# LCD_I2C.net
KiCad netlist of a schematic drawn in EAGLE
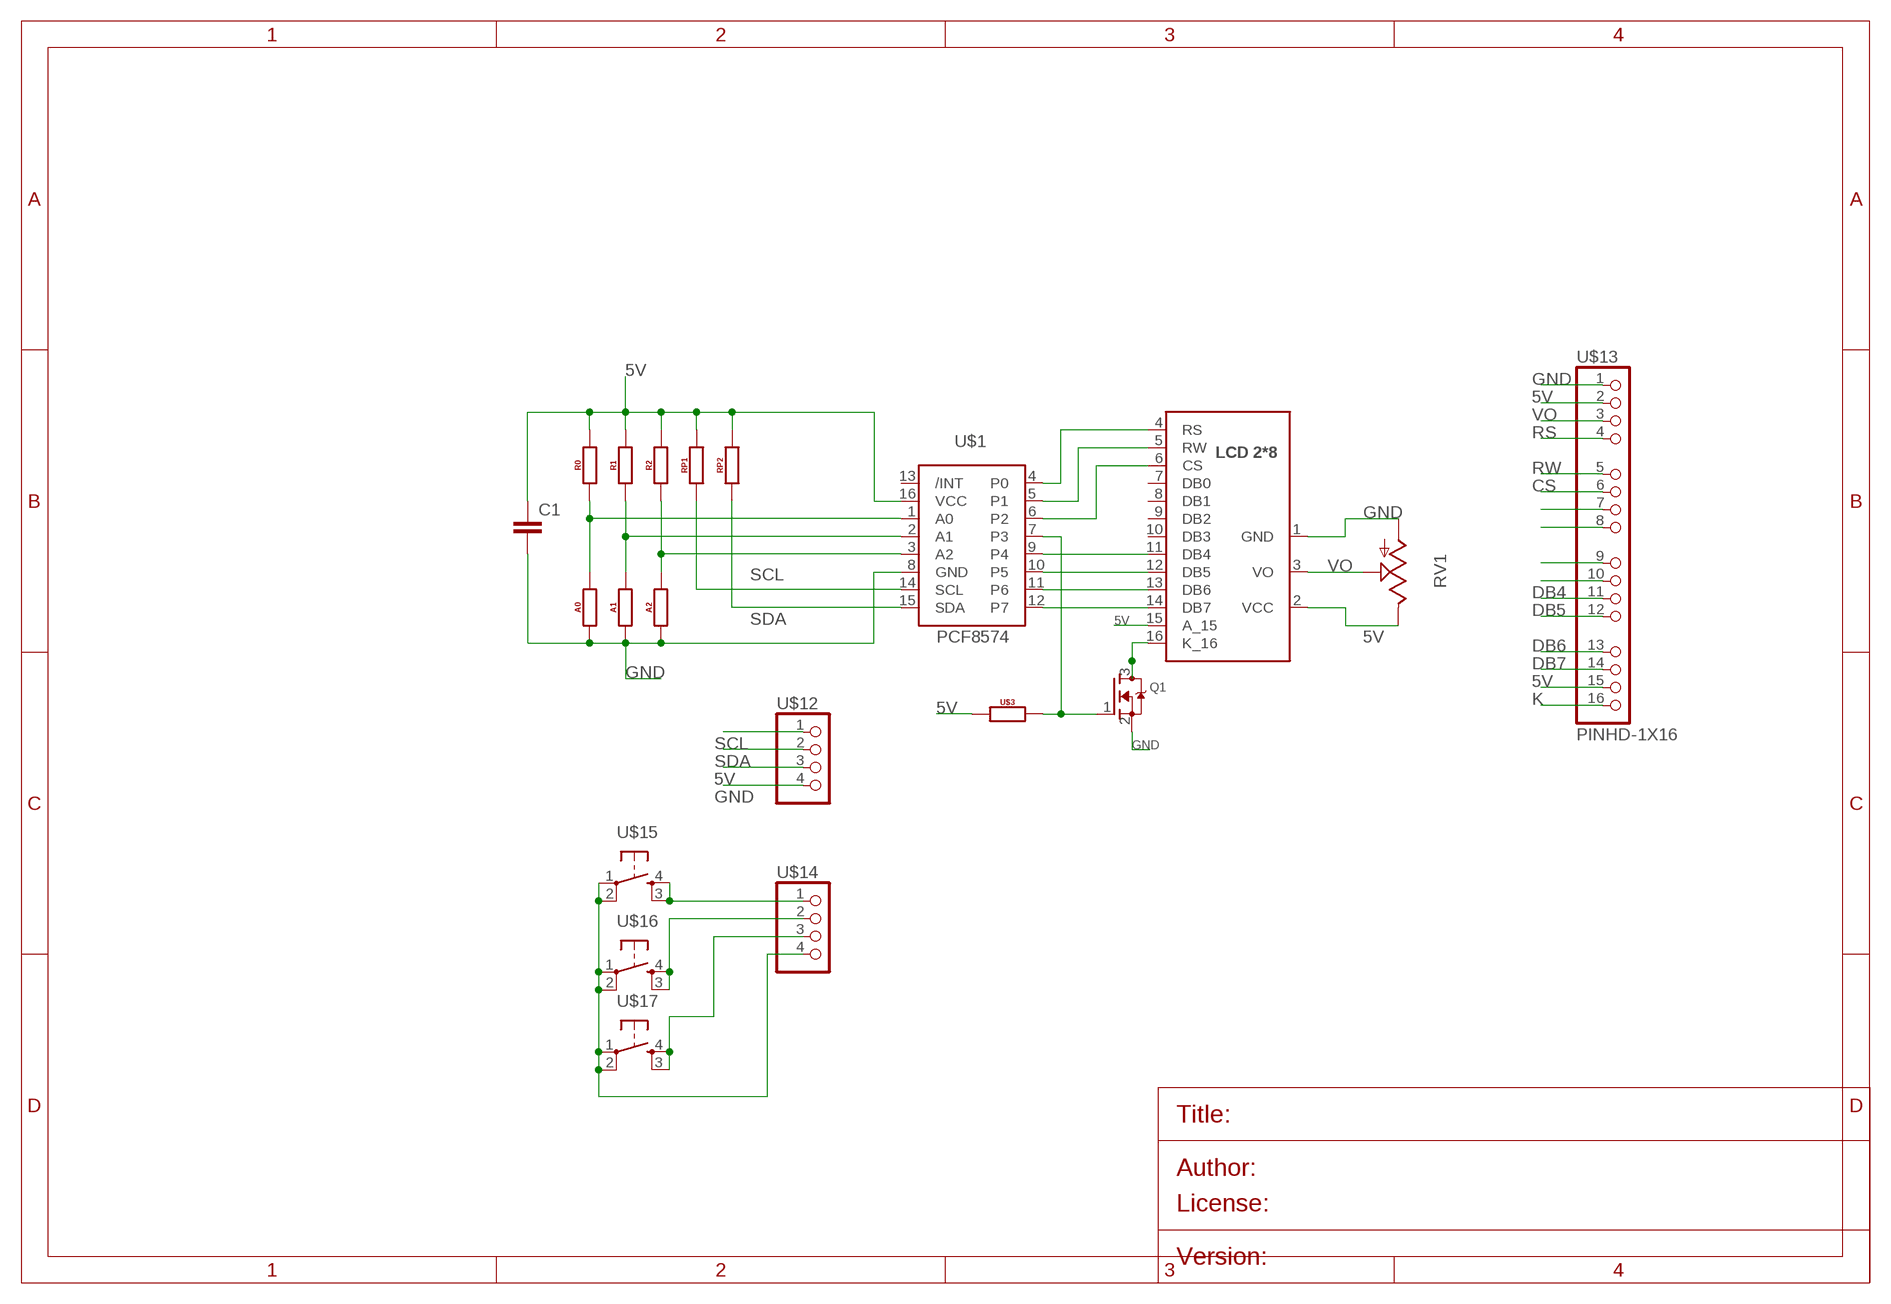
[diagram p0: schematic, sheet 1]

(export (version "E")
  (design (tool "Eeschema 10.0.6"))
  (components
    (comp (ref "A0")
      (value "RESISTOR0805")
      (footprint "eagle-import:0805")
      (libsource (lib "eagle-import") (part "RESISTOR0805"))
    )
    (comp (ref "A1")
      (value "RESISTOR0805")
      (footprint "eagle-import:0805")
      (libsource (lib "eagle-import") (part "RESISTOR0805"))
    )
    (comp (ref "A2")
      (value "RESISTOR0805")
      (footprint "eagle-import:0805")
      (libsource (lib "eagle-import") (part "RESISTOR0805"))
    )
    (comp (ref "C1")
      (value "CAPACITOR0805")
      (footprint "eagle-import:0805")
      (libsource (lib "eagle-import") (part "CAPACITOR0805"))
    )
    (comp (ref "Q1")
      (value "MOSFET-N")
      (footprint "eagle-import:SOT23-WIDE")
      (libsource (lib "eagle-import") (part "MOSFET-N"))
    )
    (comp (ref "R0")
      (value "RESISTOR0805")
      (footprint "eagle-import:0805")
      (libsource (lib "eagle-import") (part "RESISTOR0805"))
    )
    (comp (ref "R1")
      (value "RESISTOR0805")
      (footprint "eagle-import:0805")
      (libsource (lib "eagle-import") (part "RESISTOR0805"))
    )
    (comp (ref "R2")
      (value "RESISTOR0805")
      (footprint "eagle-import:0805")
      (libsource (lib "eagle-import") (part "RESISTOR0805"))
    )
    (comp (ref "RP1")
      (value "RESISTOR0805")
      (footprint "eagle-import:0805")
      (libsource (lib "eagle-import") (part "RESISTOR0805"))
    )
    (comp (ref "RP2")
      (value "RESISTOR0805")
      (footprint "eagle-import:0805")
      (libsource (lib "eagle-import") (part "RESISTOR0805"))
    )
    (comp (ref "RV1")
      (value "TRIM_POTB25P")
      (footprint "eagle-import:B25P")
      (libsource (lib "eagle-import") (part "TRIM_POTB25P"))
    )
    (comp (ref "U$1")
      (value "PCF8574")
      (footprint "eagle-import:SOIC16")
      (libsource (lib "eagle-import") (part "PCF8574"))
    )
    (comp (ref "U$2")
      (value "LCD_28_A")
      (footprint "eagle-import:LCD_2_8_A")
      (libsource (lib "eagle-import") (part "LCD_28_A"))
    )
    (comp (ref "U$3")
      (value "RESISTOR0805")
      (footprint "eagle-import:0805")
      (libsource (lib "eagle-import") (part "RESISTOR0805"))
    )
    (comp (ref "U$12")
      (value "PINHD-1X4_NO_SILK")
      (footprint "eagle-import:1X04_NO_SILK")
      (libsource (lib "eagle-import") (part "PINHD-1X4_NO_SILK"))
    )
    (comp (ref "U$13")
      (value "PINHD-1X16")
      (footprint "eagle-import:1X16_NO_SILK")
      (libsource (lib "eagle-import") (part "PINHD-1X16"))
    )
    (comp (ref "U$14")
      (value "PINHD-1X4_NO_SILK")
      (footprint "eagle-import:1X04_NO_SILK")
      (libsource (lib "eagle-import") (part "PINHD-1X4_NO_SILK"))
    )
    (comp (ref "U$15")
      (value "TACTILE_BUTTON_SMD")
      (footprint "eagle-import:TACTILE-BUTTON-SMD")
      (libsource (lib "eagle-import") (part "TACTILE_BUTTON_SMD"))
    )
    (comp (ref "U$16")
      (value "TACTILE_BUTTON_SMD")
      (footprint "eagle-import:TACTILE-BUTTON-SMD")
      (libsource (lib "eagle-import") (part "TACTILE_BUTTON_SMD"))
    )
    (comp (ref "U$17")
      (value "TACTILE_BUTTON_SMD")
      (footprint "eagle-import:TACTILE-BUTTON-SMD")
      (libsource (lib "eagle-import") (part "TACTILE_BUTTON_SMD"))
    )
  )
  (nets
    (net (code "1") (name "/5V") (class "Default")
      (node (ref "C1") (pin "1") (pinfunction "1_1") (pintype "passive"))
      (node (ref "R0") (pin "2") (pinfunction "2_2") (pintype "passive"))
      (node (ref "R1") (pin "2") (pinfunction "2_2") (pintype "passive"))
      (node (ref "R2") (pin "2") (pinfunction "2_2") (pintype "passive"))
      (node (ref "RP1") (pin "2") (pinfunction "2_2") (pintype "passive"))
      (node (ref "RP2") (pin "2") (pinfunction "2_2") (pintype "passive"))
      (node (ref "RV1") (pin "E") (pinfunction "E_E") (pintype "passive"))
      (node (ref "U$1") (pin "16") (pinfunction "VCC_16") (pintype "power_in"))
      (node (ref "U$12") (pin "3") (pinfunction "3_3") (pintype "passive"))
      (node (ref "U$13") (pin "15") (pinfunction "15_15") (pintype "passive"))
      (node (ref "U$13") (pin "2") (pinfunction "2_2") (pintype "passive"))
      (node (ref "U$2") (pin "15") (pinfunction "A_15_15") (pintype "bidirectional"))
      (node (ref "U$2") (pin "2") (pinfunction "VCC_2") (pintype "bidirectional"))
      (node (ref "U$3") (pin "1") (pinfunction "1_1") (pintype "passive"))
    )
    (net (code "2") (name "/CS") (class "Default")
      (node (ref "U$1") (pin "6") (pinfunction "P2_6") (pintype "bidirectional"))
      (node (ref "U$13") (pin "6") (pinfunction "6_6") (pintype "passive"))
      (node (ref "U$2") (pin "6") (pinfunction "CS_6") (pintype "bidirectional"))
    )
    (net (code "3") (name "/DB4") (class "Default")
      (node (ref "U$1") (pin "9") (pinfunction "P4_9") (pintype "bidirectional"))
      (node (ref "U$13") (pin "11") (pinfunction "11_11") (pintype "passive"))
      (node (ref "U$2") (pin "11") (pinfunction "DB4_11") (pintype "bidirectional"))
    )
    (net (code "4") (name "/DB5") (class "Default")
      (node (ref "U$1") (pin "10") (pinfunction "P5_10") (pintype "bidirectional"))
      (node (ref "U$13") (pin "12") (pinfunction "12_12") (pintype "passive"))
      (node (ref "U$2") (pin "12") (pinfunction "DB5_12") (pintype "bidirectional"))
    )
    (net (code "5") (name "/DB6") (class "Default")
      (node (ref "U$1") (pin "11") (pinfunction "P6_11") (pintype "bidirectional"))
      (node (ref "U$13") (pin "13") (pinfunction "13_13") (pintype "passive"))
      (node (ref "U$2") (pin "13") (pinfunction "DB6_13") (pintype "bidirectional"))
    )
    (net (code "6") (name "/DB7") (class "Default")
      (node (ref "U$1") (pin "12") (pinfunction "P7_12") (pintype "bidirectional"))
      (node (ref "U$13") (pin "14") (pinfunction "14_14") (pintype "passive"))
      (node (ref "U$2") (pin "14") (pinfunction "DB7_14") (pintype "bidirectional"))
    )
    (net (code "7") (name "/GND") (class "Default")
      (node (ref "A0") (pin "1") (pinfunction "1_1") (pintype "passive"))
      (node (ref "A1") (pin "1") (pinfunction "1_1") (pintype "passive"))
      (node (ref "A2") (pin "1") (pinfunction "1_1") (pintype "passive"))
      (node (ref "C1") (pin "2") (pinfunction "2_2") (pintype "passive"))
      (node (ref "Q1") (pin "2") (pinfunction "S_2") (pintype "bidirectional"))
      (node (ref "RV1") (pin "A") (pinfunction "A_A") (pintype "passive"))
      (node (ref "U$1") (pin "8") (pinfunction "GND_8") (pintype "power_in"))
      (node (ref "U$12") (pin "4") (pinfunction "4_4") (pintype "passive"))
      (node (ref "U$13") (pin "1") (pinfunction "1_1") (pintype "passive"))
      (node (ref "U$2") (pin "1") (pinfunction "GND_1") (pintype "bidirectional"))
    )
    (net (code "8") (name "/K") (class "Default")
      (node (ref "Q1") (pin "3") (pinfunction "D_3") (pintype "bidirectional"))
      (node (ref "U$13") (pin "16") (pinfunction "16_16") (pintype "passive"))
      (node (ref "U$2") (pin "16") (pinfunction "K_16_16") (pintype "bidirectional"))
    )
    (net (code "9") (name "/RS") (class "Default")
      (node (ref "U$1") (pin "4") (pinfunction "P0_4") (pintype "bidirectional"))
      (node (ref "U$13") (pin "4") (pinfunction "4_4") (pintype "passive"))
      (node (ref "U$2") (pin "4") (pinfunction "RS_4") (pintype "bidirectional"))
    )
    (net (code "10") (name "/RW") (class "Default")
      (node (ref "U$1") (pin "5") (pinfunction "P1_5") (pintype "bidirectional"))
      (node (ref "U$13") (pin "5") (pinfunction "5_5") (pintype "passive"))
      (node (ref "U$2") (pin "5") (pinfunction "RW_5") (pintype "bidirectional"))
    )
    (net (code "11") (name "/SCL") (class "Default")
      (node (ref "RP1") (pin "1") (pinfunction "1_1") (pintype "passive"))
      (node (ref "U$1") (pin "14") (pinfunction "SCL_14") (pintype "input"))
      (node (ref "U$12") (pin "1") (pinfunction "1_1") (pintype "passive"))
    )
    (net (code "12") (name "/SDA") (class "Default")
      (node (ref "RP2") (pin "1") (pinfunction "1_1") (pintype "passive"))
      (node (ref "U$1") (pin "15") (pinfunction "SDA_15") (pintype "bidirectional"))
      (node (ref "U$12") (pin "2") (pinfunction "2_2") (pintype "passive"))
    )
    (net (code "13") (name "/VO") (class "Default")
      (node (ref "RV1") (pin "S") (pinfunction "S_S") (pintype "passive"))
      (node (ref "U$13") (pin "3") (pinfunction "3_3") (pintype "passive"))
      (node (ref "U$2") (pin "3") (pinfunction "VO_3") (pintype "bidirectional"))
    )
    (net (code "14") (name "Net-(Q1-G)") (class "Default")
      (node (ref "Q1") (pin "1") (pinfunction "G_1") (pintype "bidirectional"))
      (node (ref "U$1") (pin "7") (pinfunction "P3_7") (pintype "bidirectional"))
      (node (ref "U$3") (pin "2") (pinfunction "2_2") (pintype "passive"))
    )
    (net (code "15") (name "Net-(U$1-A0)") (class "Default")
      (node (ref "A0") (pin "2") (pinfunction "2_2") (pintype "passive"))
      (node (ref "R0") (pin "1") (pinfunction "1_1") (pintype "passive"))
      (node (ref "U$1") (pin "1") (pinfunction "A0_1") (pintype "input"))
    )
    (net (code "16") (name "Net-(U$1-A1)") (class "Default")
      (node (ref "A1") (pin "2") (pinfunction "2_2") (pintype "passive"))
      (node (ref "R1") (pin "1") (pinfunction "1_1") (pintype "passive"))
      (node (ref "U$1") (pin "2") (pinfunction "A1_2") (pintype "input"))
    )
    (net (code "17") (name "Net-(U$1-A2)") (class "Default")
      (node (ref "A2") (pin "2") (pinfunction "2_2") (pintype "passive"))
      (node (ref "R2") (pin "1") (pinfunction "1_1") (pintype "passive"))
      (node (ref "U$1") (pin "3") (pinfunction "A2_3") (pintype "input"))
    )
    (net (code "18") (name "Net-(U$15-SWA1)") (class "Default")
      (node (ref "U$14") (pin "4") (pinfunction "4_4") (pintype "passive"))
      (node (ref "U$15") (pin "1") (pinfunction "SWA1_1") (pintype "passive"))
      (node (ref "U$15") (pin "2") (pinfunction "SWB1_2") (pintype "passive"))
      (node (ref "U$16") (pin "1") (pinfunction "SWA1_1") (pintype "passive"))
      (node (ref "U$16") (pin "2") (pinfunction "SWB1_2") (pintype "passive"))
      (node (ref "U$17") (pin "1") (pinfunction "SWA1_1") (pintype "passive"))
      (node (ref "U$17") (pin "2") (pinfunction "SWB1_2") (pintype "passive"))
    )
    (net (code "19") (name "Net-(U$15-SWA2)") (class "Default")
      (node (ref "U$14") (pin "1") (pinfunction "1_1") (pintype "passive"))
      (node (ref "U$15") (pin "3") (pinfunction "SWB2_3") (pintype "passive"))
      (node (ref "U$15") (pin "4") (pinfunction "SWA2_4") (pintype "passive"))
    )
    (net (code "20") (name "Net-(U$16-SWA2)") (class "Default")
      (node (ref "U$14") (pin "2") (pinfunction "2_2") (pintype "passive"))
      (node (ref "U$16") (pin "3") (pinfunction "SWB2_3") (pintype "passive"))
      (node (ref "U$16") (pin "4") (pinfunction "SWA2_4") (pintype "passive"))
    )
    (net (code "21") (name "Net-(U$17-SWA2)") (class "Default")
      (node (ref "U$14") (pin "3") (pinfunction "3_3") (pintype "passive"))
      (node (ref "U$17") (pin "3") (pinfunction "SWB2_3") (pintype "passive"))
      (node (ref "U$17") (pin "4") (pinfunction "SWA2_4") (pintype "passive"))
    )
    (net (code "22") (name "unconnected-(U$1-{slash}INT-Pad13)") (class "Default")
      (node (ref "U$1") (pin "13") (pinfunction "/INT_13") (pintype "output"))
    )
    (net (code "23") (name "unconnected-(U$2-DB0-Pad7)") (class "Default")
      (node (ref "U$2") (pin "7") (pinfunction "DB0_7") (pintype "bidirectional"))
    )
    (net (code "24") (name "unconnected-(U$2-DB1-Pad8)") (class "Default")
      (node (ref "U$2") (pin "8") (pinfunction "DB1_8") (pintype "bidirectional"))
    )
    (net (code "25") (name "unconnected-(U$2-DB2-Pad9)") (class "Default")
      (node (ref "U$2") (pin "9") (pinfunction "DB2_9") (pintype "bidirectional"))
    )
    (net (code "26") (name "unconnected-(U$2-DB3-Pad10)") (class "Default")
      (node (ref "U$2") (pin "10") (pinfunction "DB3_10") (pintype "bidirectional"))
    )
    (net (code "27") (name "unconnected-(U$13-Pad7)") (class "Default")
      (node (ref "U$13") (pin "7") (pinfunction "7_7") (pintype "passive"))
    )
    (net (code "28") (name "unconnected-(U$13-Pad8)") (class "Default")
      (node (ref "U$13") (pin "8") (pinfunction "8_8") (pintype "passive"))
    )
    (net (code "29") (name "unconnected-(U$13-Pad9)") (class "Default")
      (node (ref "U$13") (pin "9") (pinfunction "9_9") (pintype "passive"))
    )
    (net (code "30") (name "unconnected-(U$13-Pad10)") (class "Default")
      (node (ref "U$13") (pin "10") (pinfunction "10_10") (pintype "passive"))
    )
  )
)
